# Module_RS485_UART.net
KiCad netlist of a schematic drawn in Altium Designer
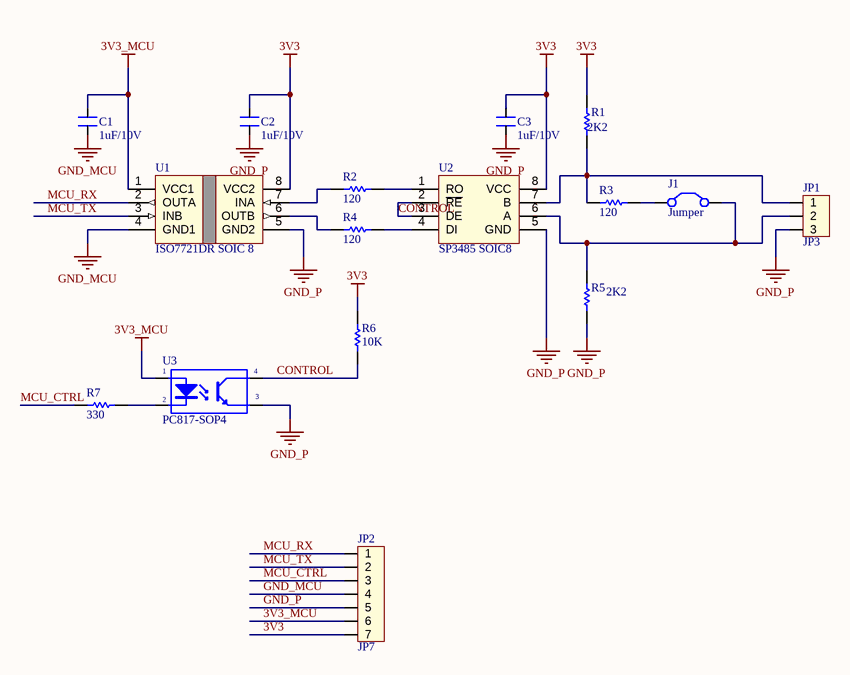
[diagram p0: Module_RS485_UART.SchDoc]

(export (version "E")
  (design (tool "Eeschema 10.0.6"))
  (components
    (comp (ref "C1")
      (value "1uF/10V")
      (footprint "Cap Ceramic 0603 SMD")
      (libsource (lib "Mach Master") (part "Cap Ceramic SMD"))
    )
    (comp (ref "C2")
      (value "1uF/10V")
      (footprint "Cap Ceramic 0603 SMD")
      (libsource (lib "Mach Master") (part "Cap Ceramic SMD"))
    )
    (comp (ref "C3")
      (value "1uF/10V")
      (footprint "Cap Ceramic 0603 SMD")
      (libsource (lib "Mach Master") (part "Cap Ceramic SMD"))
    )
    (comp (ref "J1")
      (value "Jumper")
      (footprint "Header_2")
      (description "Jumper Wire")
      (fields (field (name "PUBLISHER") "Altium Limited"))
      (libsource (lib "lpson") (part "Jumper"))
    )
    (comp (ref "JP1")
      (value "JP3")
      (footprint "2EDGR-5.08-03P")
      (description "Connector 3")
      (libsource (lib "Mach Master") (part "Con3"))
    )
    (comp (ref "JP2")
      (value "JP7")
      (footprint "CON7")
      (description "Connector 7")
      (libsource (lib "lpson") (part "Con7"))
    )
    (comp (ref "R1")
      (value "2K2")
      (footprint "Res 0603 SMD_v2")
      (description "RES SMD 249K OHM 1% 1/10W 0805")
      (fields
        (field (name "MANUFACTURER") "Yageo")
        (field (name "MANUFACTURER PART NUMBER") "RC0603FR-07249KL")
      )
      (libsource (lib "Mach Master") (part "249K/R0805/1%_2"))
    )
    (comp (ref "R2")
      (value "120")
      (footprint "Res 0603 SMD_v2")
      (description "RES SMD 249K OHM 1% 1/10W 0805")
      (fields
        (field (name "MANUFACTURER") "Yageo")
        (field (name "MANUFACTURER PART NUMBER") "RC0603FR-07249KL")
      )
      (libsource (lib "Mach Master") (part "249K/R0805/1%_2"))
    )
    (comp (ref "R3")
      (value "120")
      (footprint "Res 0603 SMD_v2")
      (description "RES SMD 249K OHM 1% 1/10W 0805")
      (fields
        (field (name "MANUFACTURER") "Yageo")
        (field (name "MANUFACTURER PART NUMBER") "RC0603FR-07249KL")
      )
      (libsource (lib "Mach Master") (part "249K/R0805/1%_2"))
    )
    (comp (ref "R4")
      (value "120")
      (footprint "Res 0603 SMD_v2")
      (description "RES SMD 249K OHM 1% 1/10W 0805")
      (fields
        (field (name "MANUFACTURER") "Yageo")
        (field (name "MANUFACTURER PART NUMBER") "RC0603FR-07249KL")
      )
      (libsource (lib "Mach Master") (part "249K/R0805/1%_2"))
    )
    (comp (ref "R5")
      (value "2K2")
      (footprint "Res 0603 SMD_v2")
      (description "RES SMD 249K OHM 1% 1/10W 0805")
      (fields
        (field (name "MANUFACTURER") "Yageo")
        (field (name "MANUFACTURER PART NUMBER") "RC0603FR-07249KL")
      )
      (libsource (lib "Mach Master") (part "249K/R0805/1%_2"))
    )
    (comp (ref "R6")
      (value "10K")
      (footprint "Res 0603 SMD_v2")
      (description "RES SMD 249K OHM 1% 1/10W 0805")
      (fields
        (field (name "MANUFACTURER") "Yageo")
        (field (name "MANUFACTURER PART NUMBER") "RC0603FR-07249KL")
      )
      (libsource (lib "Mach Master") (part "249K/R0805/1%_2"))
    )
    (comp (ref "R7")
      (value "330")
      (footprint "Res 0603 SMD_v2")
      (description "RES SMD 249K OHM 1% 1/10W 0805")
      (fields
        (field (name "MANUFACTURER") "Yageo")
        (field (name "MANUFACTURER PART NUMBER") "RC0603FR-07249KL")
      )
      (libsource (lib "Mach Master") (part "249K/R0805/1%_2"))
    )
    (comp (ref "U1")
      (value "ISO7721DR SOIC 8")
      (footprint "ISO7721D SOIC-8 10.9mm")
      (description "ISO772x High-Speed, Robust EMC, Reinforced Dual-Channel Digital Isolators")
      (libsource (lib "Mach Master") (part "ISO7721DR SOIC 8"))
    )
    (comp (ref "U2")
      (value "SP3485 SOIC8")
      (footprint "SP3485 SOIC-8 3.9mm")
      (libsource (lib "Mach Master") (part "SP3485 SOIC8"))
    )
    (comp (ref "U3")
      (value "PC817-SOP4")
      (footprint "TPC817-4SOP")
      (description "Optoisolator Transistor Output 5000Vrms 1 Channel 4-SOP")
      (libsource (lib "Mach Master") (part "PC817"))
    )
  )
  (nets
    (net (code "1") (name "/CONTROL") (class "Default")
      (node (ref "R6") (pin "2") (pinfunction "2_2") (pintype "passive"))
      (node (ref "U2") (pin "2") (pinfunction "~{RE}_2") (pintype "passive"))
      (node (ref "U2") (pin "3") (pinfunction "DE_3") (pintype "passive"))
      (node (ref "U3") (pin "4") (pinfunction "C_4") (pintype "passive"))
    )
    (net (code "2") (name "/MCU_CTRL") (class "Default")
      (node (ref "JP2") (pin "3") (pinfunction "3_3") (pintype "passive"))
      (node (ref "R7") (pin "2") (pinfunction "2_2") (pintype "passive"))
    )
    (net (code "3") (name "/MCU_RX") (class "Default")
      (node (ref "JP2") (pin "1") (pinfunction "1_1") (pintype "passive"))
      (node (ref "U1") (pin "2") (pinfunction "OUTA_2") (pintype "output"))
    )
    (net (code "4") (name "/MCU_TX") (class "Default")
      (node (ref "JP2") (pin "2") (pinfunction "2_2") (pintype "passive"))
      (node (ref "U1") (pin "3") (pinfunction "INB_3") (pintype "input"))
    )
    (net (code "5") (name "3V3") (class "Default")
      (node (ref "C2") (pin "1") (pinfunction "1_1") (pintype "passive"))
      (node (ref "C3") (pin "1") (pinfunction "1_1") (pintype "passive"))
      (node (ref "JP2") (pin "7") (pinfunction "7_7") (pintype "passive"))
      (node (ref "R1") (pin "2") (pinfunction "2_2") (pintype "passive"))
      (node (ref "R6") (pin "1") (pinfunction "1_1") (pintype "passive"))
      (node (ref "U1") (pin "8") (pinfunction "VCC2_8") (pintype "passive"))
      (node (ref "U2") (pin "8") (pinfunction "VCC_8") (pintype "passive"))
    )
    (net (code "6") (name "3V3_MCU") (class "Default")
      (node (ref "C1") (pin "1") (pinfunction "1_1") (pintype "passive"))
      (node (ref "JP2") (pin "6") (pinfunction "6_6") (pintype "passive"))
      (node (ref "U1") (pin "1") (pinfunction "VCC1_1") (pintype "passive"))
      (node (ref "U3") (pin "1") (pinfunction "A_1") (pintype "passive"))
    )
    (net (code "7") (name "GND_MCU") (class "Default")
      (node (ref "C1") (pin "2") (pinfunction "2_2") (pintype "passive"))
      (node (ref "JP2") (pin "4") (pinfunction "4_4") (pintype "passive"))
      (node (ref "U1") (pin "4") (pinfunction "GND1_4") (pintype "passive"))
    )
    (net (code "8") (name "GND_P") (class "Default")
      (node (ref "C2") (pin "2") (pinfunction "2_2") (pintype "passive"))
      (node (ref "C3") (pin "2") (pinfunction "2_2") (pintype "passive"))
      (node (ref "JP1") (pin "3") (pinfunction "3_3") (pintype "passive"))
      (node (ref "JP2") (pin "5") (pinfunction "5_5") (pintype "passive"))
      (node (ref "R5") (pin "1") (pinfunction "1_1") (pintype "passive"))
      (node (ref "U1") (pin "5") (pinfunction "GND2_5") (pintype "passive"))
      (node (ref "U2") (pin "5") (pinfunction "GND_5") (pintype "passive"))
      (node (ref "U3") (pin "3") (pinfunction "E_3") (pintype "passive"))
    )
    (net (code "9") (name "Net-(J1-C1)") (class "Default")
      (node (ref "J1") (pin "1") (pinfunction "C1_1") (pintype "passive"))
      (node (ref "R3") (pin "1") (pinfunction "1_1") (pintype "passive"))
    )
    (net (code "10") (name "Net-(J1-C2)") (class "Default")
      (node (ref "J1") (pin "2") (pinfunction "C2_2") (pintype "passive"))
      (node (ref "JP1") (pin "2") (pinfunction "2_2") (pintype "passive"))
      (node (ref "R5") (pin "2") (pinfunction "2_2") (pintype "passive"))
      (node (ref "U2") (pin "6") (pinfunction "A_6") (pintype "passive"))
    )
    (net (code "11") (name "Net-(U1-INA)") (class "Default")
      (node (ref "R2") (pin "2") (pinfunction "2_2") (pintype "passive"))
      (node (ref "U1") (pin "7") (pinfunction "INA_7") (pintype "input"))
    )
    (net (code "12") (name "Net-(U1-OUTB)") (class "Default")
      (node (ref "R4") (pin "2") (pinfunction "2_2") (pintype "passive"))
      (node (ref "U1") (pin "6") (pinfunction "OUTB_6") (pintype "output"))
    )
    (net (code "13") (name "Net-(U2-B)") (class "Default")
      (node (ref "JP1") (pin "1") (pinfunction "1_1") (pintype "passive"))
      (node (ref "R1") (pin "1") (pinfunction "1_1") (pintype "passive"))
      (node (ref "R3") (pin "2") (pinfunction "2_2") (pintype "passive"))
      (node (ref "U2") (pin "7") (pinfunction "B_7") (pintype "passive"))
    )
    (net (code "14") (name "Net-(U2-DI)") (class "Default")
      (node (ref "R4") (pin "1") (pinfunction "1_1") (pintype "passive"))
      (node (ref "U2") (pin "4") (pinfunction "DI_4") (pintype "passive"))
    )
    (net (code "15") (name "Net-(U2-RO)") (class "Default")
      (node (ref "R2") (pin "1") (pinfunction "1_1") (pintype "passive"))
      (node (ref "U2") (pin "1") (pinfunction "RO_1") (pintype "passive"))
    )
    (net (code "16") (name "Net-(U3-K)") (class "Default")
      (node (ref "R7") (pin "1") (pinfunction "1_1") (pintype "passive"))
      (node (ref "U3") (pin "2") (pinfunction "K_2") (pintype "passive"))
    )
  )
)
